# Goldfish-Voiceboard.net
KiCad netlist of a schematic drawn in EAGLE
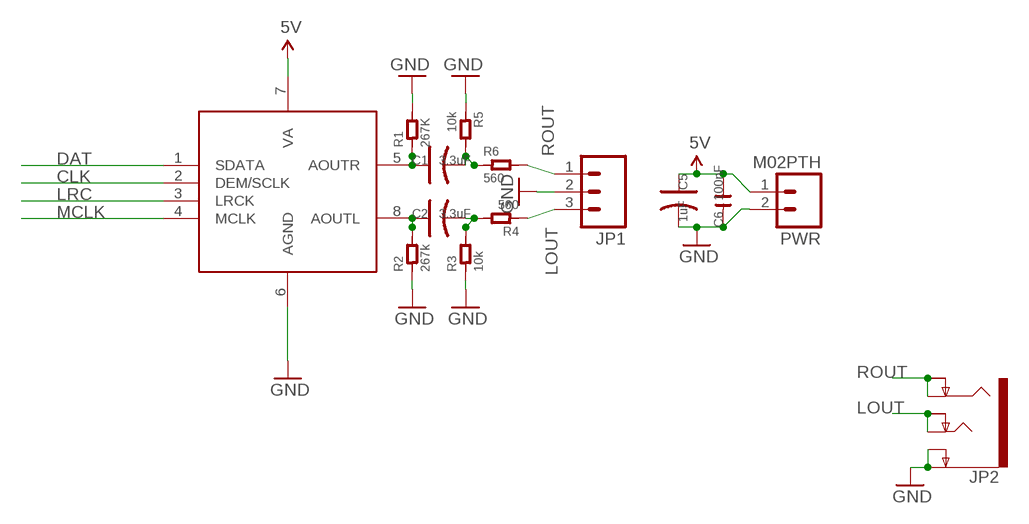
[diagram p0: schematic, sheet 1]
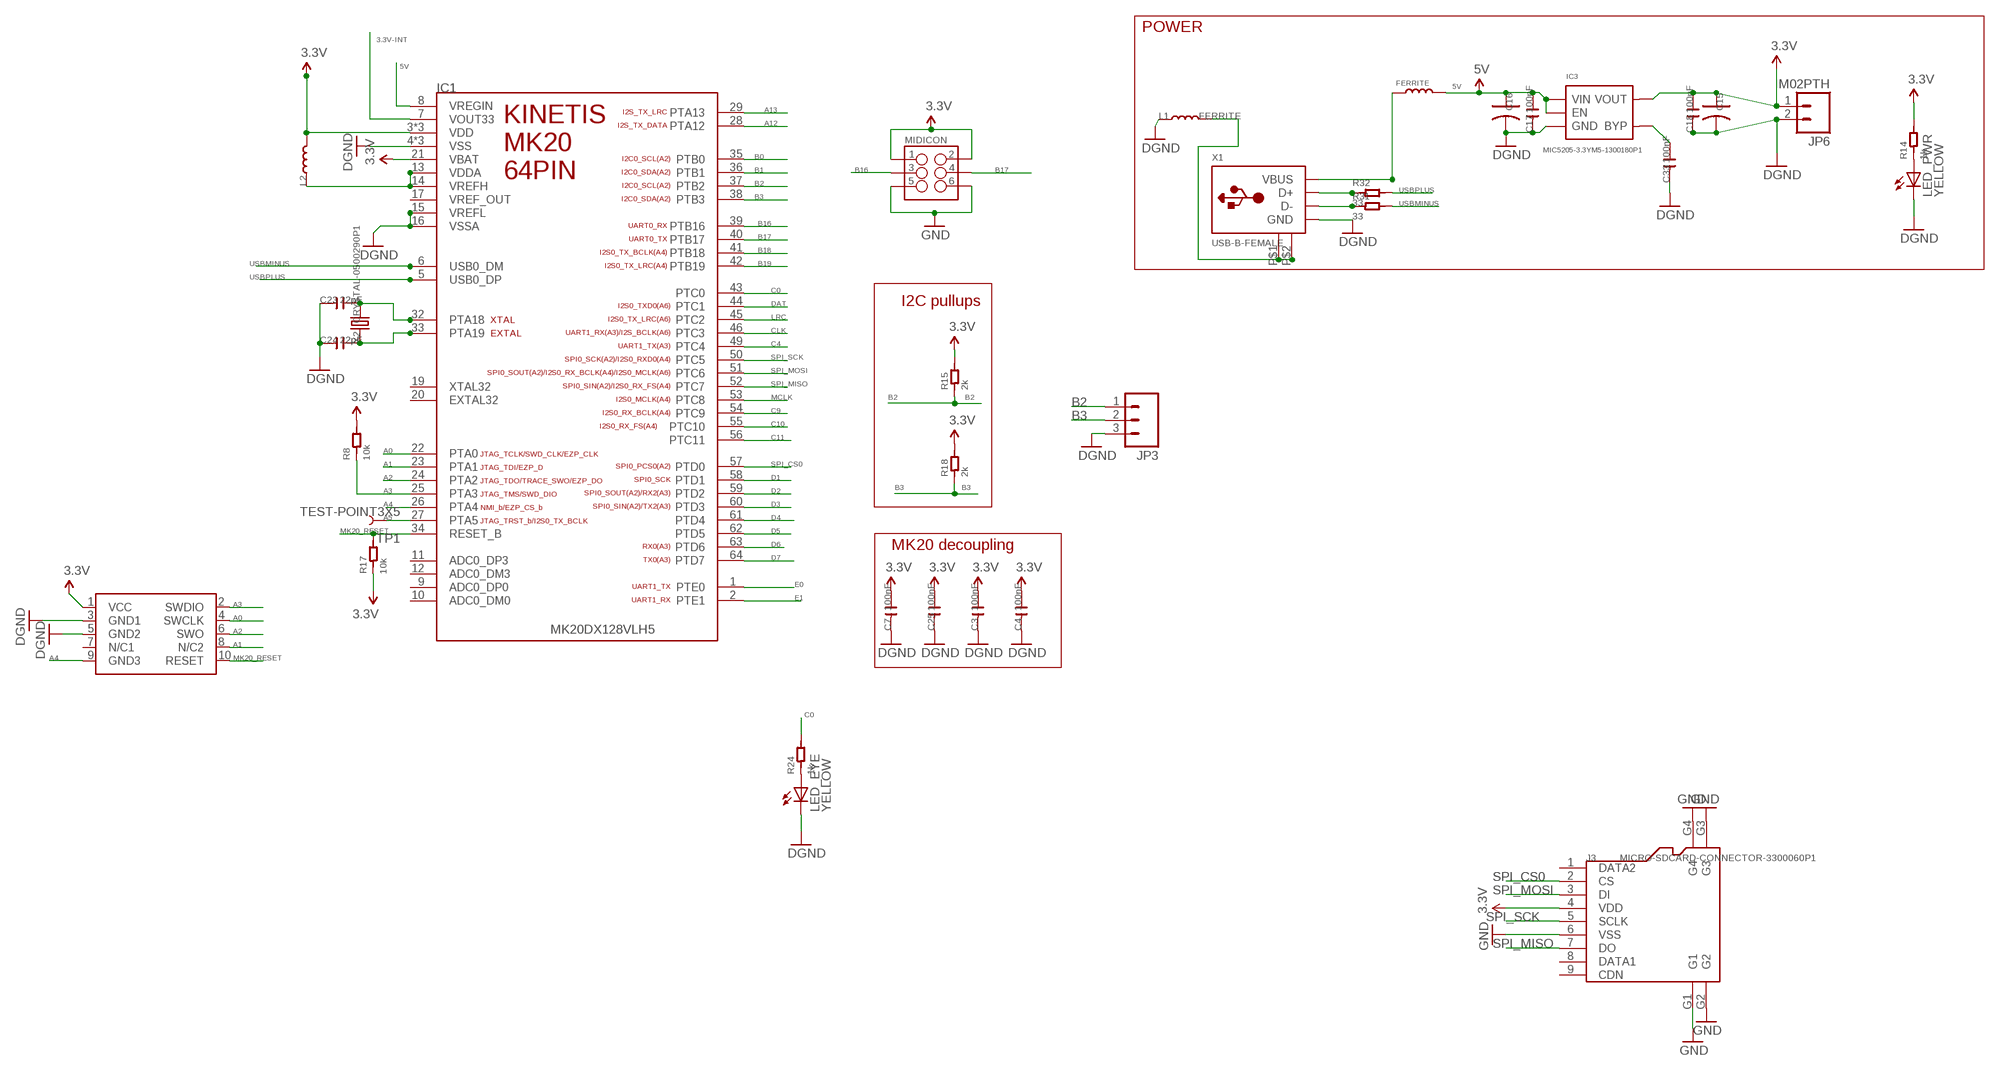
[diagram p1: schematic, sheet 2]
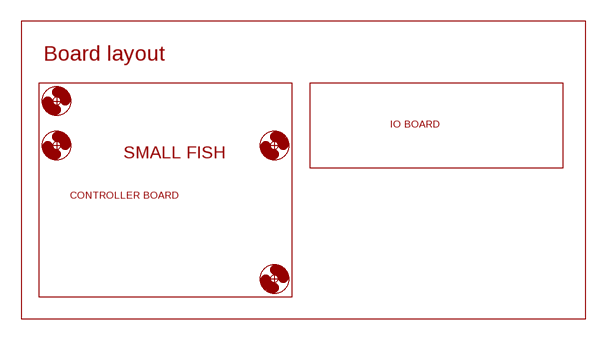
[diagram p2: schematic, sheet 3]

(export (version "E")
  (design (tool "Eeschema 10.0.6"))
  (components
    (comp (ref "C3")
      (value "100nF")
      (footprint "eagle-import:C0603")
      (libsource (lib "eagle-import") (part "OPL Eagle Library_C-0603"))
    )
    (comp (ref "C4")
      (value "100nF")
      (footprint "eagle-import:C0603")
      (libsource (lib "eagle-import") (part "OPL Eagle Library_C-0603"))
    )
    (comp (ref "C7")
      (value "100nF")
      (footprint "eagle-import:C0603")
      (libsource (lib "eagle-import") (part "OPL Eagle Library_C-0603"))
    )
    (comp (ref "C15")
      (value "C-POLAR-A")
      (footprint "eagle-import:AVX-A")
      (libsource (lib "eagle-import") (part "C-POLAR-A"))
    )
    (comp (ref "C16")
      (value "C-POLAR-A")
      (footprint "eagle-import:AVX-A")
      (libsource (lib "eagle-import") (part "C-POLAR-A"))
    )
    (comp (ref "C17")
      (value "100nF")
      (footprint "eagle-import:C0603")
      (libsource (lib "eagle-import") (part "OPL Eagle Library_C-0603"))
    )
    (comp (ref "C18")
      (value "100nF")
      (footprint "eagle-import:C0603")
      (libsource (lib "eagle-import") (part "OPL Eagle Library_C-0603"))
    )
    (comp (ref "C23")
      (value "22pF")
      (footprint "eagle-import:C0603")
      (libsource (lib "eagle-import") (part "OPL Eagle Library_C-0603"))
    )
    (comp (ref "C24")
      (value "22pF")
      (footprint "eagle-import:C0603")
      (libsource (lib "eagle-import") (part "OPL Eagle Library_C-0603"))
    )
    (comp (ref "C25")
      (value "100nF")
      (footprint "eagle-import:C0603")
      (libsource (lib "eagle-import") (part "OPL Eagle Library_C-0603"))
    )
    (comp (ref "C33")
      (value "100nF")
      (footprint "eagle-import:C0603")
      (libsource (lib "eagle-import") (part "OPL Eagle Library_C-0603"))
    )
    (comp (ref "IC1")
      (value "MK20DX128VLH5")
      (footprint "eagle-import:MK20DX128VLH5")
      (libsource (lib "eagle-import") (part "MK20DX128VLH5"))
    )
    (comp (ref "IC3")
      (value "MIC5205-3.3YM5-1300180P1")
      (footprint "eagle-import:SOT23-5")
      (libsource (lib "eagle-import") (part "MIC5205-3.3YM5-1300180P1"))
    )
    (comp (ref "J3")
      (value "MICRO-SDCARD-CONNECTOR-3300060P1")
      (footprint "eagle-import:9P-SMD-W-RING")
      (libsource (lib "eagle-import") (part "MICRO-SDCARD-CONNECTOR-3300060P1"))
    )
    (comp (ref "JP3")
      (value "M03PTH")
      (footprint "eagle-import:1X03")
      (libsource (lib "eagle-import") (part "M03PTH"))
    )
    (comp (ref "JP6")
      (value "M02PTH")
      (footprint "eagle-import:1X02")
      (libsource (lib "eagle-import") (part "M02PTH"))
    )
    (comp (ref "L1")
      (value "FERRITE")
      (footprint "eagle-import:L0603")
      (libsource (lib "eagle-import") (part "L-0603"))
    )
    (comp (ref "L2")
      (value "L-0603")
      (footprint "eagle-import:L0603")
      (libsource (lib "eagle-import") (part "L-0603"))
    )
    (comp (ref "L4")
      (value "FERRITE")
      (footprint "eagle-import:L0603")
      (libsource (lib "eagle-import") (part "L-0603"))
    )
    (comp (ref "LED_EYE")
      (value "YELLOW")
      (footprint "eagle-import:CHIP-LED0603")
      (libsource (lib "eagle-import") (part "LEDCHIP-LED0603"))
    )
    (comp (ref "LED_PWR")
      (value "YELLOW")
      (footprint "eagle-import:CHIP-LED0603")
      (libsource (lib "eagle-import") (part "LEDCHIP-LED0603"))
    )
    (comp (ref "MIDICON")
      (value "M03X2SMT")
      (footprint "eagle-import:2X3_SMT_POSTS")
      (libsource (lib "eagle-import") (part "M03X2SMT"))
    )
    (comp (ref "R8")
      (value "10k")
      (footprint "eagle-import:R0603")
      (libsource (lib "eagle-import") (part "OPL Eagle Library_R-0603"))
    )
    (comp (ref "R14")
      (value "1k")
      (footprint "eagle-import:R0603")
      (libsource (lib "eagle-import") (part "OPL Eagle Library_R-0603"))
    )
    (comp (ref "R15")
      (value "2k")
      (footprint "eagle-import:R0603")
      (libsource (lib "eagle-import") (part "R-0603"))
    )
    (comp (ref "R17")
      (value "10k")
      (footprint "eagle-import:R0603")
      (libsource (lib "eagle-import") (part "OPL Eagle Library_R-0603"))
    )
    (comp (ref "R18")
      (value "2k")
      (footprint "eagle-import:R0603")
      (libsource (lib "eagle-import") (part "R-0603"))
    )
    (comp (ref "R24")
      (value "1k")
      (footprint "eagle-import:R0603")
      (libsource (lib "eagle-import") (part "OPL Eagle Library_R-0603"))
    )
    (comp (ref "R31")
      (value "33")
      (footprint "eagle-import:R0603")
      (libsource (lib "eagle-import") (part "OPL Eagle Library_R-0603"))
    )
    (comp (ref "R32")
      (value "33")
      (footprint "eagle-import:R0603")
      (libsource (lib "eagle-import") (part "OPL Eagle Library_R-0603"))
    )
    (comp (ref "SWD1")
      (value "CORTEX_SWD")
      (footprint "eagle-import:M50-3600542")
      (libsource (lib "eagle-import") (part "CORTEX_SWD"))
    )
    (comp (ref "TP1")
      (value "TEST-POINT3X5")
      (footprint "eagle-import:PAD.03X.05")
      (libsource (lib "eagle-import") (part "TEST-POINT3X5"))
    )
    (comp (ref "X1")
      (value "USB-B-FEMALE")
      (footprint "eagle-import:FCI61729")
      (libsource (lib "eagle-import") (part "USB-B-FEMALE"))
    )
    (comp (ref "X2")
      (value "CRYSTAL-0500290P1")
      (footprint "eagle-import:2P-SMD-5.0X3.2")
      (libsource (lib "eagle-import") (part "CRYSTAL-0500290P1"))
    )
    (comp (ref "H1")
      (value "MOUNT-HOLE")
      (footprint "eagle-import:3.2-NOMARKINGS-SMALLSAFEZONE")
      (libsource (lib "eagle-import") (part "MOUNT-HOLE"))
    )
    (comp (ref "H4")
      (value "MOUNT-HOLE")
      (footprint "eagle-import:3.2-NOMARKINGS-SMALLSAFEZONE")
      (libsource (lib "eagle-import") (part "MOUNT-HOLE"))
    )
    (comp (ref "H9")
      (value "MOUNT-HOLE")
      (footprint "eagle-import:3.2-NOMARKINGS-SMALLSAFEZONE")
      (libsource (lib "eagle-import") (part "MOUNT-HOLE"))
    )
    (comp (ref "H10")
      (value "MOUNT-HOLE")
      (footprint "eagle-import:3.2-NOMARKINGS-SMALLSAFEZONE")
      (libsource (lib "eagle-import") (part "MOUNT-HOLE"))
    )
    (comp (ref "U$11")
      (value "FISH_SMALL")
      (footprint "eagle-import:FISH_SMALL")
      (libsource (lib "eagle-import") (part "FISH_SMALL"))
    )
    (comp (ref "C1")
      (value "3.3uF")
      (footprint "eagle-import:AVX-A")
      (libsource (lib "eagle-import") (part "C-POLAR-A"))
    )
    (comp (ref "C2")
      (value "3.3uF")
      (footprint "eagle-import:AVX-A")
      (libsource (lib "eagle-import") (part "C-POLAR-A"))
    )
    (comp (ref "C5")
      (value "1uF")
      (footprint "eagle-import:AVX-A")
      (libsource (lib "eagle-import") (part "C-POLAR-A"))
    )
    (comp (ref "C6")
      (value "100nF")
      (footprint "eagle-import:C0603")
      (libsource (lib "eagle-import") (part "C-0603"))
    )
    (comp (ref "JP1")
      (value "M03PTH")
      (footprint "eagle-import:1X03")
      (libsource (lib "eagle-import") (part "M03PTH"))
    )
    (comp (ref "JP2")
      (value "AUDIO-JACK4-.25-HORIZ-TRS")
      (footprint "eagle-import:AUDIO-JACK-.25-INCH-HORIZ-PTH")
      (libsource (lib "eagle-import") (part "AUDIO-JACK4-.25-HORIZ-TRS"))
    )
    (comp (ref "PWR")
      (value "M02PTH")
      (footprint "eagle-import:1X02")
      (libsource (lib "eagle-import") (part "M02PTH"))
    )
    (comp (ref "R1")
      (value "267K")
      (footprint "eagle-import:R0603")
      (libsource (lib "eagle-import") (part "R-0603"))
    )
    (comp (ref "R2")
      (value "267k")
      (footprint "eagle-import:R0603")
      (libsource (lib "eagle-import") (part "R-0603"))
    )
    (comp (ref "R3")
      (value "10k")
      (footprint "eagle-import:R0603")
      (libsource (lib "eagle-import") (part "R-0603"))
    )
    (comp (ref "R4")
      (value "560")
      (footprint "eagle-import:R0603")
      (libsource (lib "eagle-import") (part "R-0603"))
    )
    (comp (ref "R5")
      (value "10k")
      (footprint "eagle-import:R0603")
      (libsource (lib "eagle-import") (part "R-0603"))
    )
    (comp (ref "R6")
      (value "560")
      (footprint "eagle-import:R0603")
      (libsource (lib "eagle-import") (part "R-0603"))
    )
    (comp (ref "U$1")
      (value "CS4335-KSZ")
      (footprint "eagle-import:SOIC8_208MIL")
      (libsource (lib "eagle-import") (part "CS4335-KSZ"))
    )
  )
  (nets
    (net (code "1") (name "3.3V") (class "Default")
      (node (ref "C15") (pin "+") (pinfunction "1_+") (pintype "bidirectional"))
      (node (ref "C18") (pin "2") (pinfunction "2_2") (pintype "bidirectional"))
      (node (ref "C25") (pin "2") (pinfunction "2_2") (pintype "bidirectional"))
      (node (ref "C3") (pin "2") (pinfunction "2_2") (pintype "bidirectional"))
      (node (ref "C4") (pin "2") (pinfunction "2_2") (pintype "bidirectional"))
      (node (ref "C7") (pin "2") (pinfunction "2_2") (pintype "bidirectional"))
      (node (ref "IC1") (pin "21") (pinfunction "VBAT_21") (pintype "bidirectional"))
      (node (ref "IC1") (pin "3") (pinfunction "VDD_3") (pintype "bidirectional"))
      (node (ref "IC1") (pin "30") (pinfunction "VDD_30") (pintype "bidirectional"))
      (node (ref "IC1") (pin "48") (pinfunction "VDD_48") (pintype "bidirectional"))
      (node (ref "IC3") (pin "5") (pinfunction "VOUT_5") (pintype "bidirectional"))
      (node (ref "J3") (pin "4") (pinfunction "VDD_4") (pintype "bidirectional"))
      (node (ref "JP6") (pin "1") (pinfunction "1_1") (pintype "passive"))
      (node (ref "L2") (pin "2") (pinfunction "2_2") (pintype "passive"))
      (node (ref "MIDICON") (pin "1") (pinfunction "1_1") (pintype "bidirectional"))
      (node (ref "MIDICON") (pin "2") (pinfunction "2_2") (pintype "bidirectional"))
      (node (ref "R14") (pin "2") (pinfunction "2_2") (pintype "bidirectional"))
      (node (ref "R15") (pin "2") (pinfunction "2_2") (pintype "bidirectional"))
      (node (ref "R17") (pin "1") (pinfunction "1_1") (pintype "bidirectional"))
      (node (ref "R18") (pin "2") (pinfunction "2_2") (pintype "bidirectional"))
      (node (ref "R8") (pin "2") (pinfunction "2_2") (pintype "bidirectional"))
      (node (ref "SWD1") (pin "1") (pinfunction "VCC_1") (pintype "bidirectional"))
    )
    (net (code "2") (name "3.3V-INT") (class "Default")
      (node (ref "IC1") (pin "7") (pinfunction "VOUT33_7") (pintype "bidirectional"))
    )
    (net (code "3") (name "5V") (class "Default")
      (node (ref "C16") (pin "+") (pinfunction "1_+") (pintype "bidirectional"))
      (node (ref "C17") (pin "2") (pinfunction "2_2") (pintype "bidirectional"))
      (node (ref "C5") (pin "+") (pinfunction "1_+") (pintype "bidirectional"))
      (node (ref "C6") (pin "2") (pinfunction "2_2") (pintype "bidirectional"))
      (node (ref "IC1") (pin "8") (pinfunction "VREGIN_8") (pintype "bidirectional"))
      (node (ref "IC3") (pin "1") (pinfunction "VIN_1") (pintype "bidirectional"))
      (node (ref "IC3") (pin "3") (pinfunction "EN_3") (pintype "bidirectional"))
      (node (ref "L4") (pin "2") (pinfunction "2_2") (pintype "passive"))
      (node (ref "PWR") (pin "1") (pinfunction "1_1") (pintype "passive"))
      (node (ref "U$1") (pin "7") (pinfunction "VA_7") (pintype "bidirectional"))
    )
    (net (code "4") (name "A0") (class "Default")
      (node (ref "IC1") (pin "22") (pinfunction "PTA0_22") (pintype "bidirectional"))
      (node (ref "SWD1") (pin "4") (pinfunction "SWCLK_4") (pintype "bidirectional"))
    )
    (net (code "5") (name "A1") (class "Default")
      (node (ref "IC1") (pin "23") (pinfunction "PTA1_23") (pintype "bidirectional"))
      (node (ref "SWD1") (pin "8") (pinfunction "N/C2_8") (pintype "bidirectional"))
    )
    (net (code "6") (name "A2") (class "Default")
      (node (ref "IC1") (pin "24") (pinfunction "PTA2_24") (pintype "bidirectional"))
      (node (ref "SWD1") (pin "6") (pinfunction "SWO_6") (pintype "bidirectional"))
    )
    (net (code "7") (name "A3") (class "Default")
      (node (ref "IC1") (pin "25") (pinfunction "PTA3_25") (pintype "bidirectional"))
      (node (ref "R8") (pin "1") (pinfunction "1_1") (pintype "bidirectional"))
      (node (ref "SWD1") (pin "2") (pinfunction "SWDIO_2") (pintype "bidirectional"))
    )
    (net (code "8") (name "A4") (class "Default")
      (node (ref "IC1") (pin "26") (pinfunction "PTA4_26") (pintype "bidirectional"))
      (node (ref "SWD1") (pin "9") (pinfunction "GND3_9") (pintype "bidirectional"))
    )
    (net (code "9") (name "A5") (class "Default")
      (node (ref "IC1") (pin "27") (pinfunction "PTA5_27") (pintype "bidirectional"))
      (node (ref "TP1") (pin "P$1") (pinfunction "1_P$1") (pintype "bidirectional"))
    )
    (net (code "10") (name "A12") (class "Default")
      (node (ref "IC1") (pin "28") (pinfunction "PTA12_28") (pintype "bidirectional"))
    )
    (net (code "11") (name "A13") (class "Default")
      (node (ref "IC1") (pin "29") (pinfunction "PTA13_29") (pintype "bidirectional"))
    )
    (net (code "12") (name "B0") (class "Default")
      (node (ref "IC1") (pin "35") (pinfunction "PTB0_35") (pintype "bidirectional"))
    )
    (net (code "13") (name "B1") (class "Default")
      (node (ref "IC1") (pin "36") (pinfunction "PTB1_36") (pintype "bidirectional"))
    )
    (net (code "14") (name "B2") (class "Default")
      (node (ref "IC1") (pin "37") (pinfunction "PTB2_37") (pintype "bidirectional"))
      (node (ref "JP3") (pin "1") (pinfunction "1_1") (pintype "passive"))
      (node (ref "R15") (pin "1") (pinfunction "1_1") (pintype "bidirectional"))
    )
    (net (code "15") (name "B3") (class "Default")
      (node (ref "IC1") (pin "38") (pinfunction "PTB3_38") (pintype "bidirectional"))
      (node (ref "JP3") (pin "2") (pinfunction "2_2") (pintype "passive"))
      (node (ref "R18") (pin "1") (pinfunction "1_1") (pintype "bidirectional"))
    )
    (net (code "16") (name "B16") (class "Default")
      (node (ref "IC1") (pin "39") (pinfunction "PTB16_39") (pintype "bidirectional"))
      (node (ref "MIDICON") (pin "3") (pinfunction "3_3") (pintype "bidirectional"))
    )
    (net (code "17") (name "B17") (class "Default")
      (node (ref "IC1") (pin "40") (pinfunction "PTB17_40") (pintype "bidirectional"))
      (node (ref "MIDICON") (pin "4") (pinfunction "4_4") (pintype "bidirectional"))
    )
    (net (code "18") (name "B18") (class "Default")
      (node (ref "IC1") (pin "41") (pinfunction "PTB18_41") (pintype "bidirectional"))
    )
    (net (code "19") (name "B19") (class "Default")
      (node (ref "IC1") (pin "42") (pinfunction "PTB19_42") (pintype "bidirectional"))
    )
    (net (code "20") (name "C0") (class "Default")
      (node (ref "IC1") (pin "43") (pinfunction "PTC0_43") (pintype "bidirectional"))
      (node (ref "R24") (pin "2") (pinfunction "2_2") (pintype "bidirectional"))
    )
    (net (code "21") (name "C4") (class "Default")
      (node (ref "IC1") (pin "49") (pinfunction "PTC4_49") (pintype "bidirectional"))
    )
    (net (code "22") (name "C9") (class "Default")
      (node (ref "IC1") (pin "54") (pinfunction "PTC9_54") (pintype "bidirectional"))
    )
    (net (code "23") (name "C10") (class "Default")
      (node (ref "IC1") (pin "55") (pinfunction "PTC10_55") (pintype "bidirectional"))
    )
    (net (code "24") (name "C11") (class "Default")
      (node (ref "IC1") (pin "56") (pinfunction "PTC11_56") (pintype "bidirectional"))
    )
    (net (code "25") (name "CLK") (class "Default")
      (node (ref "IC1") (pin "46") (pinfunction "PTC3_46") (pintype "bidirectional"))
      (node (ref "U$1") (pin "2") (pinfunction "DEM/SCLK_2") (pintype "bidirectional"))
    )
    (net (code "26") (name "D1") (class "Default")
      (node (ref "IC1") (pin "58") (pinfunction "PTD1_58") (pintype "bidirectional"))
    )
    (net (code "27") (name "D2") (class "Default")
      (node (ref "IC1") (pin "59") (pinfunction "PTD2_59") (pintype "bidirectional"))
    )
    (net (code "28") (name "D3") (class "Default")
      (node (ref "IC1") (pin "60") (pinfunction "PTD3_60") (pintype "bidirectional"))
    )
    (net (code "29") (name "D4") (class "Default")
      (node (ref "IC1") (pin "61") (pinfunction "PTD4_61") (pintype "bidirectional"))
    )
    (net (code "30") (name "D5") (class "Default")
      (node (ref "IC1") (pin "62") (pinfunction "PTD5_62") (pintype "bidirectional"))
    )
    (net (code "31") (name "D6") (class "Default")
      (node (ref "IC1") (pin "63") (pinfunction "PTD6_63") (pintype "bidirectional"))
    )
    (net (code "32") (name "D7") (class "Default")
      (node (ref "IC1") (pin "64") (pinfunction "PTD7_64") (pintype "bidirectional"))
    )
    (net (code "33") (name "DAT") (class "Default")
      (node (ref "IC1") (pin "44") (pinfunction "PTC1_44") (pintype "bidirectional"))
      (node (ref "U$1") (pin "1") (pinfunction "SDATA_1") (pintype "bidirectional"))
    )
    (net (code "34") (name "E0") (class "Default")
      (node (ref "IC1") (pin "1") (pinfunction "PTE0_1") (pintype "bidirectional"))
    )
    (net (code "35") (name "E1") (class "Default")
      (node (ref "IC1") (pin "2") (pinfunction "PTE1_2") (pintype "bidirectional"))
    )
    (net (code "36") (name "GND") (class "Default")
      (node (ref "C15") (pin "-") (pinfunction "2_-") (pintype "bidirectional"))
      (node (ref "C16") (pin "-") (pinfunction "2_-") (pintype "bidirectional"))
      (node (ref "C17") (pin "1") (pinfunction "1_1") (pintype "bidirectional"))
      (node (ref "C18") (pin "1") (pinfunction "1_1") (pintype "bidirectional"))
      (node (ref "C23") (pin "1") (pinfunction "1_1") (pintype "bidirectional"))
      (node (ref "C24") (pin "1") (pinfunction "1_1") (pintype "bidirectional"))
      (node (ref "C25") (pin "1") (pinfunction "1_1") (pintype "bidirectional"))
      (node (ref "C3") (pin "1") (pinfunction "1_1") (pintype "bidirectional"))
      (node (ref "C33") (pin "1") (pinfunction "1_1") (pintype "bidirectional"))
      (node (ref "C4") (pin "1") (pinfunction "1_1") (pintype "bidirectional"))
      (node (ref "C5") (pin "-") (pinfunction "2_-") (pintype "bidirectional"))
      (node (ref "C6") (pin "1") (pinfunction "1_1") (pintype "bidirectional"))
      (node (ref "C7") (pin "1") (pinfunction "1_1") (pintype "bidirectional"))
      (node (ref "IC1") (pin "15") (pinfunction "VREFL_15") (pintype "bidirectional"))
      (node (ref "IC1") (pin "16") (pinfunction "VSSA_16") (pintype "bidirectional"))
      (node (ref "IC1") (pin "31") (pinfunction "VSS_31") (pintype "bidirectional"))
      (node (ref "IC1") (pin "4") (pinfunction "VSS_4") (pintype "bidirectional"))
      (node (ref "IC1") (pin "47") (pinfunction "VSS_47") (pintype "bidirectional"))
      (node (ref "IC3") (pin "2") (pinfunction "GND_2") (pintype "bidirectional"))
      (node (ref "J3") (pin "6") (pinfunction "VSS_6") (pintype "bidirectional"))
      (node (ref "J3") (pin "G1") (pinfunction "G1_G1") (pintype "bidirectional"))
      (node (ref "J3") (pin "G2") (pinfunction "G2_G2") (pintype "bidirectional"))
      (node (ref "J3") (pin "G3") (pinfunction "G3_G3") (pintype "bidirectional"))
      (node (ref "J3") (pin "G4") (pinfunction "G4_G4") (pintype "bidirectional"))
      (node (ref "JP1") (pin "2") (pinfunction "2_2") (pintype "passive"))
      (node (ref "JP2") (pin "P$2") (pinfunction "EARTH_P$2") (pintype "bidirectional"))
      (node (ref "JP2") (pin "P$3") (pinfunction "EARTH-NORM_P$3") (pintype "bidirectional"))
      (node (ref "JP3") (pin "3") (pinfunction "3_3") (pintype "passive"))
      (node (ref "JP6") (pin "2") (pinfunction "2_2") (pintype "passive"))
      (node (ref "L1") (pin "1") (pinfunction "1_1") (pintype "passive"))
      (node (ref "LED_EYE") (pin "C") (pinfunction "C_C") (pintype "passive"))
      (node (ref "LED_PWR") (pin "C") (pinfunction "C_C") (pintype "passive"))
      (node (ref "MIDICON") (pin "5") (pinfunction "5_5") (pintype "bidirectional"))
      (node (ref "MIDICON") (pin "6") (pinfunction "6_6") (pintype "bidirectional"))
      (node (ref "PWR") (pin "2") (pinfunction "2_2") (pintype "passive"))
      (node (ref "R1") (pin "2") (pinfunction "2_2") (pintype "bidirectional"))
      (node (ref "R2") (pin "1") (pinfunction "1_1") (pintype "bidirectional"))
      (node (ref "R3") (pin "1") (pinfunction "1_1") (pintype "bidirectional"))
      (node (ref "R5") (pin "1") (pinfunction "1_1") (pintype "bidirectional"))
      (node (ref "SWD1") (pin "3") (pinfunction "GND1_3") (pintype "bidirectional"))
      (node (ref "SWD1") (pin "5") (pinfunction "GND2_5") (pintype "bidirectional"))
      (node (ref "U$1") (pin "6") (pinfunction "AGND_6") (pintype "bidirectional"))
      (node (ref "X1") (pin "4") (pinfunction "GND_4") (pintype "power_in"))
    )
    (net (code "37") (name "LOUT") (class "Default")
      (node (ref "JP1") (pin "3") (pinfunction "3_3") (pintype "passive"))
      (node (ref "JP2") (pin "P$6") (pinfunction "TIP_P$6") (pintype "bidirectional"))
      (node (ref "JP2") (pin "P$7") (pinfunction "TIP-NORM_P$7") (pintype "bidirectional"))
      (node (ref "R4") (pin "1") (pinfunction "1_1") (pintype "bidirectional"))
    )
    (net (code "38") (name "LRC") (class "Default")
      (node (ref "IC1") (pin "45") (pinfunction "PTC2_45") (pintype "bidirectional"))
      (node (ref "U$1") (pin "3") (pinfunction "LRCK_3") (pintype "bidirectional"))
    )
    (net (code "39") (name "MCLK") (class "Default")
      (node (ref "IC1") (pin "53") (pinfunction "PTC8_53") (pintype "bidirectional"))
      (node (ref "U$1") (pin "4") (pinfunction "MCLK_4") (pintype "bidirectional"))
    )
    (net (code "40") (name "MK20_RESET") (class "Default")
      (node (ref "IC1") (pin "34") (pinfunction "RESET_B_34") (pintype "bidirectional"))
      (node (ref "R17") (pin "2") (pinfunction "2_2") (pintype "bidirectional"))
      (node (ref "SWD1") (pin "10") (pinfunction "RESET_10") (pintype "bidirectional"))
    )
    (net (code "41") (name "Net-(C1-1)") (class "Default")
      (node (ref "C1") (pin "+") (pinfunction "1_+") (pintype "bidirectional"))
      (node (ref "R1") (pin "1") (pinfunction "1_1") (pintype "bidirectional"))
      (node (ref "U$1") (pin "5") (pinfunction "AOUTR_5") (pintype "bidirectional"))
    )
    (net (code "42") (name "Net-(C1-2)") (class "Default")
      (node (ref "C1") (pin "-") (pinfunction "2_-") (pintype "bidirectional"))
      (node (ref "R5") (pin "2") (pinfunction "2_2") (pintype "bidirectional"))
      (node (ref "R6") (pin "1") (pinfunction "1_1") (pintype "bidirectional"))
    )
    (net (code "43") (name "Net-(C2-1)") (class "Default")
      (node (ref "C2") (pin "+") (pinfunction "1_+") (pintype "bidirectional"))
      (node (ref "R2") (pin "2") (pinfunction "2_2") (pintype "bidirectional"))
      (node (ref "U$1") (pin "8") (pinfunction "AOUTL_8") (pintype "bidirectional"))
    )
    (net (code "44") (name "Net-(C2-2)") (class "Default")
      (node (ref "C2") (pin "-") (pinfunction "2_-") (pintype "bidirectional"))
      (node (ref "R3") (pin "2") (pinfunction "2_2") (pintype "bidirectional"))
      (node (ref "R4") (pin "2") (pinfunction "2_2") (pintype "bidirectional"))
    )
    (net (code "45") (name "Net-(IC1-PTA18)") (class "Default")
      (node (ref "C23") (pin "2") (pinfunction "2_2") (pintype "bidirectional"))
      (node (ref "IC1") (pin "32") (pinfunction "PTA18_32") (pintype "bidirectional"))
      (node (ref "X2") (pin "2") (pinfunction "2_2") (pintype "passive"))
    )
    (net (code "46") (name "Net-(IC1-PTA19)") (class "Default")
      (node (ref "C24") (pin "2") (pinfunction "2_2") (pintype "bidirectional"))
      (node (ref "IC1") (pin "33") (pinfunction "PTA19_33") (pintype "bidirectional"))
      (node (ref "X2") (pin "1") (pinfunction "1_1") (pintype "passive"))
    )
    (net (code "47") (name "Net-(IC1-VDDA)") (class "Default")
      (node (ref "IC1") (pin "13") (pinfunction "VDDA_13") (pintype "bidirectional"))
      (node (ref "IC1") (pin "14") (pinfunction "VREFH_14") (pintype "bidirectional"))
      (node (ref "L2") (pin "1") (pinfunction "1_1") (pintype "passive"))
    )
    (net (code "48") (name "Net-(IC3-BYP)") (class "Default")
      (node (ref "C33") (pin "2") (pinfunction "2_2") (pintype "bidirectional"))
      (node (ref "IC3") (pin "4") (pinfunction "BYP_4") (pintype "bidirectional"))
    )
    (net (code "49") (name "Net-(LED_EYE-PadA)") (class "Default")
      (node (ref "LED_EYE") (pin "A") (pinfunction "A_A") (pintype "passive"))
      (node (ref "R24") (pin "1") (pinfunction "1_1") (pintype "bidirectional"))
    )
    (net (code "50") (name "Net-(LED_PWR-PadA)") (class "Default")
      (node (ref "LED_PWR") (pin "A") (pinfunction "A_A") (pintype "passive"))
      (node (ref "R14") (pin "1") (pinfunction "1_1") (pintype "bidirectional"))
    )
    (net (code "51") (name "Net-(X1-D+)") (class "Default")
      (node (ref "R32") (pin "1") (pinfunction "1_1") (pintype "bidirectional"))
      (node (ref "X1") (pin "3") (pinfunction "D+_3") (pintype "bidirectional"))
    )
    (net (code "52") (name "Net-(X1-D-)") (class "Default")
      (node (ref "R31") (pin "1") (pinfunction "1_1") (pintype "bidirectional"))
      (node (ref "X1") (pin "2") (pinfunction "D-_2") (pintype "bidirectional"))
    )
    (net (code "53") (name "Net-(X1-GND1)") (class "Default")
      (node (ref "L1") (pin "2") (pinfunction "2_2") (pintype "passive"))
      (node (ref "X1") (pin "P$1") (pinfunction "GND1_P$1") (pintype "power_in"))
      (node (ref "X1") (pin "P$2") (pinfunction "GND2_P$2") (pintype "power_in"))
    )
    (net (code "54") (name "Net-(X1-VBUS)") (class "Default")
      (node (ref "L4") (pin "1") (pinfunction "1_1") (pintype "passive"))
      (node (ref "X1") (pin "1") (pinfunction "VBUS_1") (pintype "power_in"))
    )
    (net (code "55") (name "ROUT") (class "Default")
      (node (ref "JP1") (pin "1") (pinfunction "1_1") (pintype "passive"))
      (node (ref "JP2") (pin "P$4") (pinfunction "RING_P$4") (pintype "bidirectional"))
      (node (ref "JP2") (pin "P$5") (pinfunction "RING-NORM_P$5") (pintype "bidirectional"))
      (node (ref "R6") (pin "2") (pinfunction "2_2") (pintype "bidirectional"))
    )
    (net (code "56") (name "SPI_CS0") (class "Default")
      (node (ref "IC1") (pin "57") (pinfunction "PTD0_57") (pintype "bidirectional"))
      (node (ref "J3") (pin "2") (pinfunction "CS_2") (pintype "bidirectional"))
    )
    (net (code "57") (name "SPI_MISO") (class "Default")
      (node (ref "IC1") (pin "52") (pinfunction "PTC7_52") (pintype "bidirectional"))
      (node (ref "J3") (pin "7") (pinfunction "DO_7") (pintype "bidirectional"))
    )
    (net (code "58") (name "SPI_MOSI") (class "Default")
      (node (ref "IC1") (pin "51") (pinfunction "PTC6_51") (pintype "bidirectional"))
      (node (ref "J3") (pin "3") (pinfunction "DI_3") (pintype "bidirectional"))
    )
    (net (code "59") (name "SPI_SCK") (class "Default")
      (node (ref "IC1") (pin "50") (pinfunction "PTC5_50") (pintype "bidirectional"))
      (node (ref "J3") (pin "5") (pinfunction "SCLK_5") (pintype "bidirectional"))
    )
    (net (code "60") (name "USBMINUS") (class "Default")
      (node (ref "IC1") (pin "6") (pinfunction "USB0_DM_6") (pintype "bidirectional"))
      (node (ref "R31") (pin "2") (pinfunction "2_2") (pintype "bidirectional"))
    )
    (net (code "61") (name "USBPLUS") (class "Default")
      (node (ref "IC1") (pin "5") (pinfunction "USB0_DP_5") (pintype "bidirectional"))
      (node (ref "R32") (pin "2") (pinfunction "2_2") (pintype "bidirectional"))
    )
    (net (code "62") (name "unconnected-(IC1-ADC0_DM0-Pad10)") (class "Default")
      (node (ref "IC1") (pin "10") (pinfunction "ADC0_DM0_10") (pintype "bidirectional"))
    )
    (net (code "63") (name "unconnected-(IC1-ADC0_DM3-Pad12)") (class "Default")
      (node (ref "IC1") (pin "12") (pinfunction "ADC0_DM3_12") (pintype "bidirectional"))
    )
    (net (code "64") (name "unconnected-(IC1-ADC0_DP0-Pad9)") (class "Default")
      (node (ref "IC1") (pin "9") (pinfunction "ADC0_DP0_9") (pintype "bidirectional"))
    )
    (net (code "65") (name "unconnected-(IC1-ADC0_DP3-Pad11)") (class "Default")
      (node (ref "IC1") (pin "11") (pinfunction "ADC0_DP3_11") (pintype "bidirectional"))
    )
    (net (code "66") (name "unconnected-(IC1-EXTAL32-Pad20)") (class "Default")
      (node (ref "IC1") (pin "20") (pinfunction "EXTAL32_20") (pintype "bidirectional"))
    )
    (net (code "67") (name "unconnected-(IC1-VREF_OUT-Pad17)") (class "Default")
      (node (ref "IC1") (pin "17") (pinfunction "VREF_OUT_17") (pintype "bidirectional"))
    )
    (net (code "68") (name "unconnected-(IC1-XTAL32-Pad19)") (class "Default")
      (node (ref "IC1") (pin "19") (pinfunction "XTAL32_19") (pintype "bidirectional"))
    )
    (net (code "69") (name "unconnected-(J3-CDN-Pad9)") (class "Default")
      (node (ref "J3") (pin "9") (pinfunction "CDN_9") (pintype "bidirectional"))
    )
    (net (code "70") (name "unconnected-(J3-DATA1-Pad8)") (class "Default")
      (node (ref "J3") (pin "8") (pinfunction "DATA1_8") (pintype "bidirectional"))
    )
    (net (code "71") (name "unconnected-(J3-DATA2-Pad1)") (class "Default")
      (node (ref "J3") (pin "1") (pinfunction "DATA2_1") (pintype "bidirectional"))
    )
    (net (code "72") (name "unconnected-(SWD1-N{slash}C1-Pad7)") (class "Default")
      (node (ref "SWD1") (pin "7") (pinfunction "N/C1_7") (pintype "bidirectional"))
    )
  )
)
